# SCH_PCB-Hacker-Card-070924_2024-07-11.net
KiCad netlist of a schematic drawn in EasyEDA
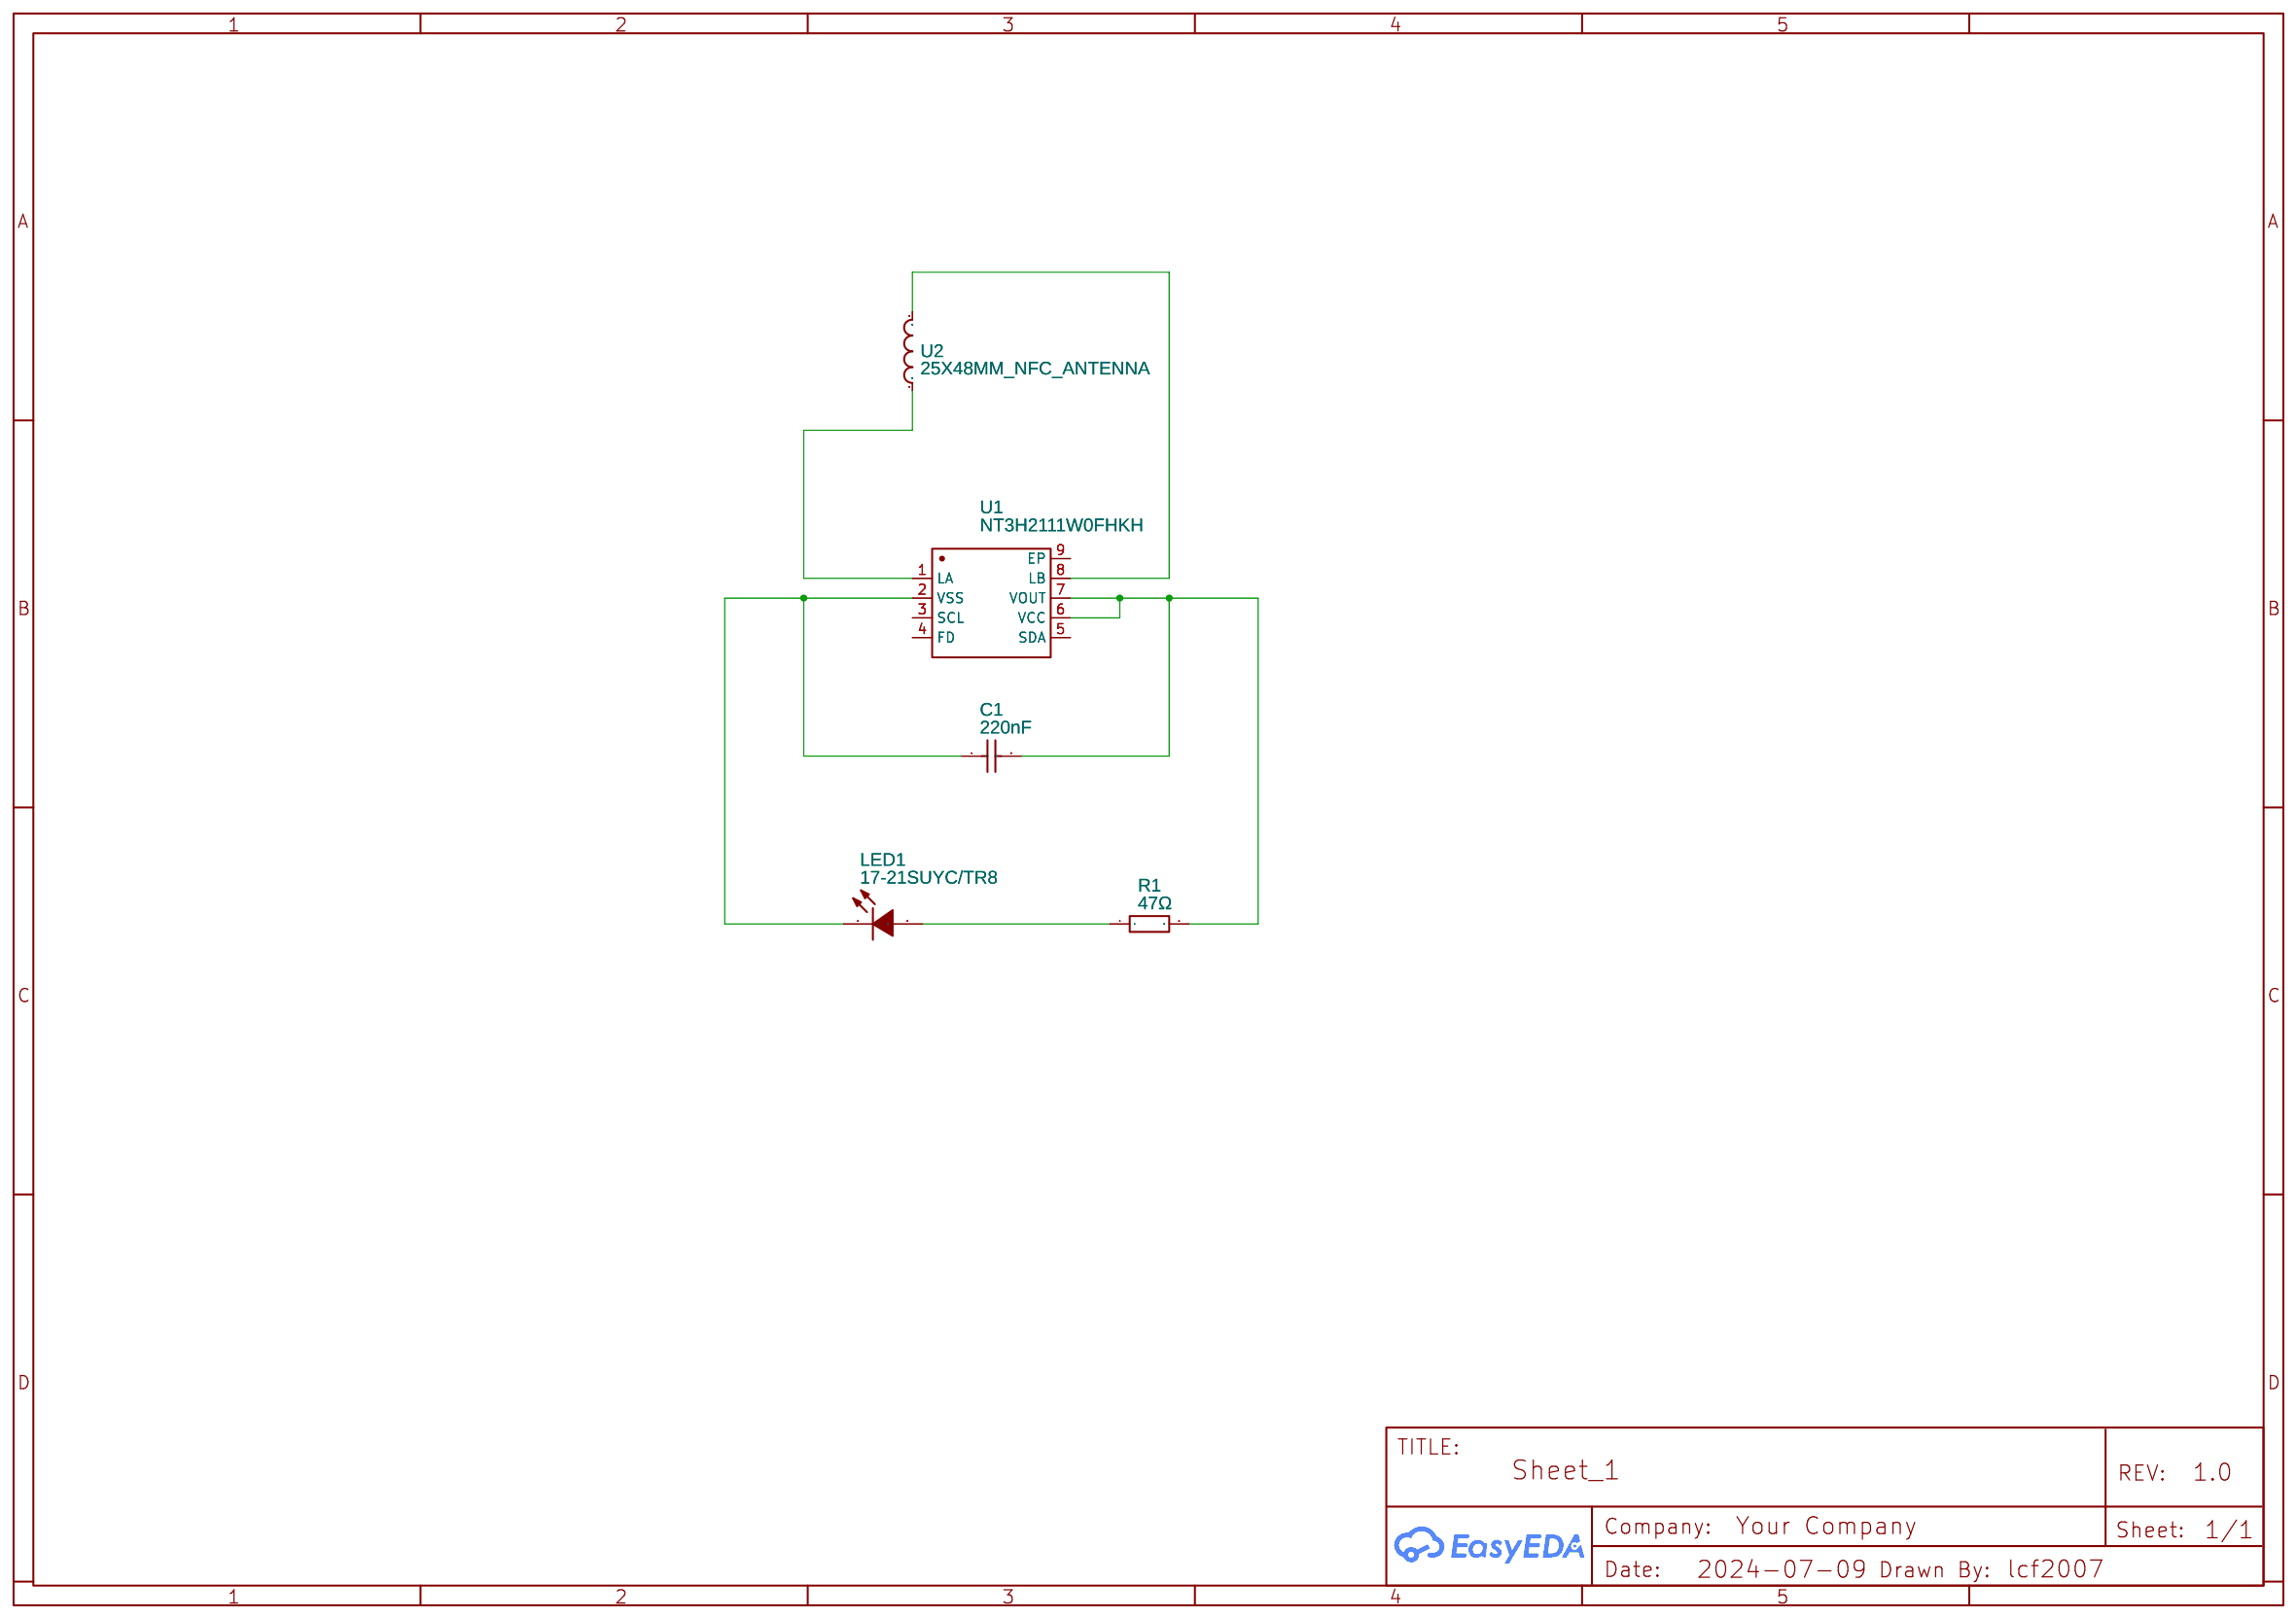
[diagram p0: schematic sheet]

(export (version "E")
  (design (tool "Eeschema 10.0.6"))
  (components
    (comp (ref "C1")
      (value "220nF")
      (fields
        (field (name "Manufacturer Part") "CL10B224KA8NNNC")
        (field (name "Manufacturer") "SAMSUNG(三星)")
      )
      (libsource (lib "") (part "CL10B224KA8NNNC"))
    )
    (comp (ref "LED1")
      (value "17-21SUYC/TR8")
      (fields (field (name "Manufacturer Part") "KT-0805黄灯") (field (name "Manufacturer") "KENTO"))
      (libsource (lib "") (part "17-21SUYC/TR8"))
    )
    (comp (ref "R1")
      (value "47Ω")
      (fields
        (field (name "Manufacturer Part") "0603WAF470JT5E")
        (field (name "Manufacturer") "UNI-ROYAL(厚声)")
      )
      (libsource (lib "") (part "0603WAF470JT5E"))
    )
    (comp (ref "U1")
      (value "NT3H2111W0FHKH")
      (fields (field (name "Manufacturer") "NXP(恩智浦)"))
      (libsource (lib "") (part "NT3H2111W0FHKH"))
    )
    (comp (ref "U2") (value "25X48MM_NFC_ANTENNA") (libsource (lib "") (part "25X48MM_NFC_ANTENNA")))
  )
  (nets
    (net (code "1") (name "Net-(LED1-+)") (class "Default")
      (node (ref "LED1") (pin "1") (pinfunction "+_1") (pintype "unspecified"))
      (node (ref "R1") (pin "1") (pinfunction "1_1") (pintype "input"))
    )
    (net (code "2") (name "Net-(LED1--)") (class "Default")
      (node (ref "C1") (pin "1") (pinfunction "1_1") (pintype "input"))
      (node (ref "LED1") (pin "2") (pinfunction "-_2") (pintype "unspecified"))
      (node (ref "U1") (pin "2") (pinfunction "VSS_2") (pintype "unspecified"))
    )
    (net (code "3") (name "Net-(U1-LA)") (class "Default")
      (node (ref "U1") (pin "1") (pinfunction "LA_1") (pintype "unspecified"))
      (node (ref "U2") (pin "1") (pinfunction "1_1") (pintype "unspecified"))
    )
    (net (code "4") (name "Net-(U1-LB)") (class "Default")
      (node (ref "U1") (pin "8") (pinfunction "LB_8") (pintype "unspecified"))
      (node (ref "U2") (pin "2") (pinfunction "2_2") (pintype "unspecified"))
    )
    (net (code "5") (name "Net-(U1-VCC)") (class "Default")
      (node (ref "C1") (pin "2") (pinfunction "2_2") (pintype "input"))
      (node (ref "R1") (pin "2") (pinfunction "2_2") (pintype "input"))
      (node (ref "U1") (pin "6") (pinfunction "VCC_6") (pintype "unspecified"))
      (node (ref "U1") (pin "7") (pinfunction "VOUT_7") (pintype "unspecified"))
    )
    (net (code "6") (name "unconnected-(U1-EP-Pad9)") (class "Default")
      (node (ref "U1") (pin "9") (pinfunction "EP_9") (pintype "unspecified"))
    )
    (net (code "7") (name "unconnected-(U1-FD-Pad4)") (class "Default")
      (node (ref "U1") (pin "4") (pinfunction "FD_4") (pintype "unspecified"))
    )
    (net (code "8") (name "unconnected-(U1-SCL-Pad3)") (class "Default")
      (node (ref "U1") (pin "3") (pinfunction "SCL_3") (pintype "unspecified"))
    )
    (net (code "9") (name "unconnected-(U1-SDA-Pad5)") (class "Default")
      (node (ref "U1") (pin "5") (pinfunction "SDA_5") (pintype "unspecified"))
    )
  )
)
